# analog_v10.net
KiCad netlist of a schematic drawn in EAGLE
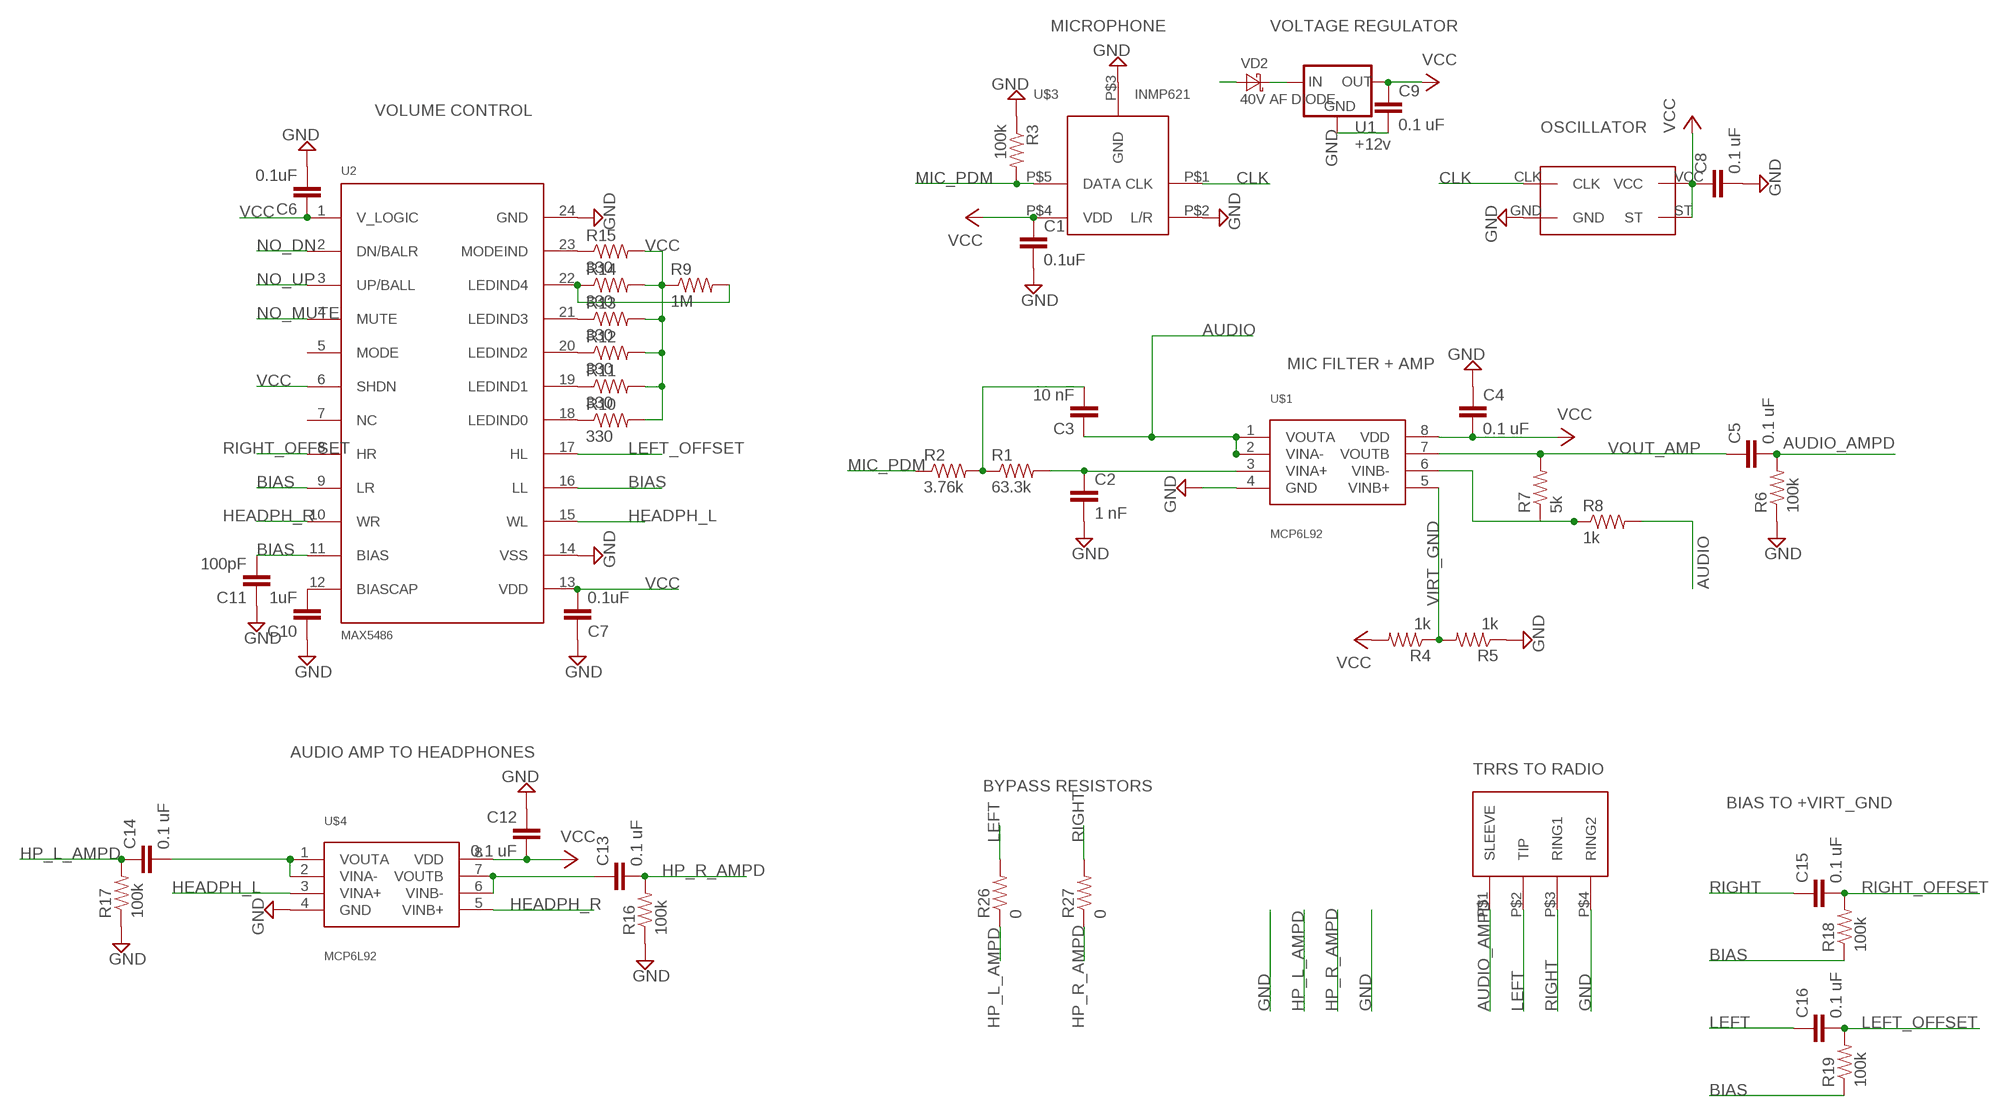
[diagram p0: schematic, sheet 1]

(export (version "E")
  (design (tool "Eeschema 10.0.6"))
  (components
    (comp (ref "C1")
      (value "0.1uF")
      (footprint "eagle-import:0805")
      (libsource (lib "eagle-import") (part "CAP0805"))
    )
    (comp (ref "C2")
      (value "1 nF")
      (footprint "eagle-import:0805")
      (libsource (lib "eagle-import") (part "CAP0805"))
    )
    (comp (ref "C3")
      (value "10 nF")
      (footprint "eagle-import:0805")
      (libsource (lib "eagle-import") (part "CAP0805"))
    )
    (comp (ref "C4")
      (value "0.1 uF")
      (footprint "eagle-import:0805")
      (libsource (lib "eagle-import") (part "CAP0805"))
    )
    (comp (ref "C5")
      (value "0.1 uF")
      (footprint "eagle-import:0805")
      (libsource (lib "eagle-import") (part "CAP0805"))
    )
    (comp (ref "C6")
      (value "0.1uF")
      (footprint "eagle-import:0805")
      (libsource (lib "eagle-import") (part "CAP0805"))
    )
    (comp (ref "C7")
      (value "0.1uF")
      (footprint "eagle-import:0805")
      (libsource (lib "eagle-import") (part "CAP0805"))
    )
    (comp (ref "C8")
      (value "0.1 uF")
      (footprint "eagle-import:0805")
      (libsource (lib "eagle-import") (part "CAP0805"))
    )
    (comp (ref "C9")
      (value "0.1 uF")
      (footprint "eagle-import:0805")
      (libsource (lib "eagle-import") (part "CAP0805"))
    )
    (comp (ref "C10")
      (value "1uF")
      (footprint "eagle-import:0805")
      (libsource (lib "eagle-import") (part "CAP0805"))
    )
    (comp (ref "C11")
      (value "100pF")
      (footprint "eagle-import:0805")
      (libsource (lib "eagle-import") (part "CAP0805"))
    )
    (comp (ref "C12")
      (value "0.1 uF")
      (footprint "eagle-import:0805")
      (libsource (lib "eagle-import") (part "CAP0805"))
    )
    (comp (ref "C13")
      (value "0.1 uF")
      (footprint "eagle-import:0805")
      (libsource (lib "eagle-import") (part "CAP0805"))
    )
    (comp (ref "C14")
      (value "0.1 uF")
      (footprint "eagle-import:0805")
      (libsource (lib "eagle-import") (part "CAP0805"))
    )
    (comp (ref "C15")
      (value "0.1 uF")
      (footprint "eagle-import:0805")
      (libsource (lib "eagle-import") (part "CAP0805"))
    )
    (comp (ref "C16")
      (value "0.1 uF")
      (footprint "eagle-import:0805")
      (libsource (lib "eagle-import") (part "CAP0805"))
    )
    (comp (ref "R1")
      (value "63.3k")
      (footprint "eagle-import:0805")
      (libsource (lib "eagle-import") (part "RESISTOR0805-RES"))
    )
    (comp (ref "R2")
      (value "3.76k")
      (footprint "eagle-import:0805")
      (libsource (lib "eagle-import") (part "RESISTOR0805-RES"))
    )
    (comp (ref "R3")
      (value "100k")
      (footprint "eagle-import:0805")
      (libsource (lib "eagle-import") (part "RESISTOR0805-RES"))
    )
    (comp (ref "R4")
      (value "1k")
      (footprint "eagle-import:0805")
      (libsource (lib "eagle-import") (part "RESISTOR0805-RES"))
    )
    (comp (ref "R5")
      (value "1k")
      (footprint "eagle-import:0805")
      (libsource (lib "eagle-import") (part "RESISTOR0805-RES"))
    )
    (comp (ref "R6")
      (value "100k")
      (footprint "eagle-import:0805")
      (libsource (lib "eagle-import") (part "SparkFun-Resistors_RESISTOR0805-RES"))
    )
    (comp (ref "R7")
      (value "5k")
      (footprint "eagle-import:0805")
      (libsource (lib "eagle-import") (part "SparkFun-Resistors_RESISTOR0805-RES"))
    )
    (comp (ref "R8")
      (value "1k")
      (footprint "eagle-import:0805")
      (libsource (lib "eagle-import") (part "SparkFun-Resistors_RESISTOR0805-RES"))
    )
    (comp (ref "R9")
      (value "1M")
      (footprint "eagle-import:0805")
      (libsource (lib "eagle-import") (part "RESISTOR0805-RES"))
    )
    (comp (ref "R10")
      (value "330")
      (footprint "eagle-import:0805")
      (libsource (lib "eagle-import") (part "RESISTOR0805-RES"))
    )
    (comp (ref "R11")
      (value "330")
      (footprint "eagle-import:0805")
      (libsource (lib "eagle-import") (part "RESISTOR0805-RES"))
    )
    (comp (ref "R12")
      (value "330")
      (footprint "eagle-import:0805")
      (libsource (lib "eagle-import") (part "RESISTOR0805-RES"))
    )
    (comp (ref "R13")
      (value "330")
      (footprint "eagle-import:0805")
      (libsource (lib "eagle-import") (part "RESISTOR0805-RES"))
    )
    (comp (ref "R14")
      (value "330")
      (footprint "eagle-import:0805")
      (libsource (lib "eagle-import") (part "RESISTOR0805-RES"))
    )
    (comp (ref "R15")
      (value "330")
      (footprint "eagle-import:0805")
      (libsource (lib "eagle-import") (part "RESISTOR0805-RES"))
    )
    (comp (ref "R16")
      (value "100k")
      (footprint "eagle-import:0805")
      (libsource (lib "eagle-import") (part "SparkFun-Resistors_RESISTOR0805-RES"))
    )
    (comp (ref "R17")
      (value "100k")
      (footprint "eagle-import:0805")
      (libsource (lib "eagle-import") (part "SparkFun-Resistors_RESISTOR0805-RES"))
    )
    (comp (ref "R18")
      (value "100k")
      (footprint "eagle-import:0805")
      (libsource (lib "eagle-import") (part "SparkFun-Resistors_RESISTOR0805-RES"))
    )
    (comp (ref "R19")
      (value "100k")
      (footprint "eagle-import:0805")
      (libsource (lib "eagle-import") (part "SparkFun-Resistors_RESISTOR0805-RES"))
    )
    (comp (ref "R26")
      (value "0")
      (footprint "eagle-import:0805")
      (libsource (lib "eagle-import") (part "RESISTOR0805-RES"))
    )
    (comp (ref "R27")
      (value "0")
      (footprint "eagle-import:0805")
      (libsource (lib "eagle-import") (part "RESISTOR0805-RES"))
    )
    (comp (ref "RADIO")
      (value "SJ-43514-SMT")
      (footprint "eagle-import:35MM_SMD_4WIRE")
      (libsource (lib "eagle-import") (part "SJ-43514-SMT"))
    )
    (comp (ref "U$1")
      (value "MCP6L92")
      (footprint "eagle-import:MSOP8")
      (libsource (lib "eagle-import") (part "MCP6L92"))
    )
    (comp (ref "U$2")
      (value "SG-210STF")
      (footprint "eagle-import:SG-210STF")
      (libsource (lib "eagle-import") (part "SG-210STF"))
    )
    (comp (ref "U$3")
      (value "INMP621")
      (footprint "eagle-import:CUSTOM_MIC")
      (libsource (lib "eagle-import") (part "INMP621"))
    )
    (comp (ref "U$4")
      (value "MCP6L92")
      (footprint "eagle-import:MSOP8")
      (libsource (lib "eagle-import") (part "MCP6L92"))
    )
    (comp (ref "U1")
      (value "+12v")
      (footprint "eagle-import:TO-252")
      (libsource (lib "eagle-import") (part "V_REG_78XX7812"))
    )
    (comp (ref "U2")
      (value "MAX5486")
      (footprint "eagle-import:TSSOP24")
      (libsource (lib "eagle-import") (part "MAX5486"))
    )
    (comp (ref "VD2")
      (value "40V AF DIODE")
      (footprint "eagle-import:SOD123")
      (libsource (lib "eagle-import") (part "DIODE-SCHOTTKY-SOD123"))
    )
  )
  (nets
    (net (code "1") (name "/AUDIO") (class "Default")
      (node (ref "C3") (pin "1") (pinfunction "1_1") (pintype "passive"))
      (node (ref "R8") (pin "2") (pinfunction "2_2") (pintype "passive"))
      (node (ref "U$1") (pin "1") (pinfunction "VOUTA_1") (pintype "bidirectional"))
      (node (ref "U$1") (pin "2") (pinfunction "VINA-_2") (pintype "bidirectional"))
    )
    (net (code "2") (name "/AUDIO_AMPD") (class "Default")
      (node (ref "C5") (pin "2") (pinfunction "2_2") (pintype "passive"))
      (node (ref "R6") (pin "2") (pinfunction "2_2") (pintype "passive"))
      (node (ref "RADIO") (pin "P$1") (pinfunction "SLEEVE_P$1") (pintype "bidirectional"))
    )
    (net (code "3") (name "/BIAS") (class "Default")
      (node (ref "C11") (pin "2") (pinfunction "2_2") (pintype "passive"))
      (node (ref "R18") (pin "1") (pinfunction "1_1") (pintype "passive"))
      (node (ref "R19") (pin "1") (pinfunction "1_1") (pintype "passive"))
      (node (ref "U2") (pin "11") (pinfunction "BIAS_11") (pintype "bidirectional"))
      (node (ref "U2") (pin "16") (pinfunction "LL_16") (pintype "input"))
      (node (ref "U2") (pin "9") (pinfunction "LR_9") (pintype "output"))
    )
    (net (code "4") (name "/CLK") (class "Default")
      (node (ref "U$2") (pin "CLK") (pinfunction "CLK_CLK") (pintype "bidirectional"))
      (node (ref "U$3") (pin "P$1") (pinfunction "CLK_P$1") (pintype "bidirectional"))
    )
    (net (code "5") (name "/HEADPH_L") (class "Default")
      (node (ref "U$4") (pin "3") (pinfunction "VINA+_3") (pintype "bidirectional"))
      (node (ref "U2") (pin "15") (pinfunction "WL_15") (pintype "power_in"))
    )
    (net (code "6") (name "/HEADPH_R") (class "Default")
      (node (ref "U$4") (pin "5") (pinfunction "VINB+_5") (pintype "bidirectional"))
      (node (ref "U2") (pin "10") (pinfunction "WR_10") (pintype "output"))
    )
    (net (code "7") (name "/HP_L_AMPD") (class "Default")
      (node (ref "C14") (pin "1") (pinfunction "1_1") (pintype "passive"))
      (node (ref "R17") (pin "2") (pinfunction "2_2") (pintype "passive"))
      (node (ref "R26") (pin "1") (pinfunction "1_1") (pintype "passive"))
    )
    (net (code "8") (name "/HP_R_AMPD") (class "Default")
      (node (ref "C13") (pin "2") (pinfunction "2_2") (pintype "passive"))
      (node (ref "R16") (pin "2") (pinfunction "2_2") (pintype "passive"))
      (node (ref "R27") (pin "1") (pinfunction "1_1") (pintype "passive"))
    )
    (net (code "9") (name "/LEFT") (class "Default")
      (node (ref "C16") (pin "1") (pinfunction "1_1") (pintype "passive"))
      (node (ref "R26") (pin "2") (pinfunction "2_2") (pintype "passive"))
      (node (ref "RADIO") (pin "P$2") (pinfunction "TIP_P$2") (pintype "bidirectional"))
    )
    (net (code "10") (name "/LEFT_OFFSET") (class "Default")
      (node (ref "C16") (pin "2") (pinfunction "2_2") (pintype "passive"))
      (node (ref "R19") (pin "2") (pinfunction "2_2") (pintype "passive"))
      (node (ref "U2") (pin "17") (pinfunction "HL_17") (pintype "input"))
    )
    (net (code "11") (name "/MIC_PDM") (class "Default")
      (node (ref "R2") (pin "1") (pinfunction "1_1") (pintype "passive"))
      (node (ref "R3") (pin "2") (pinfunction "2_2") (pintype "passive"))
      (node (ref "U$3") (pin "P$5") (pinfunction "DATA_P$5") (pintype "bidirectional"))
    )
    (net (code "12") (name "/NO_DN") (class "Default")
      (node (ref "U2") (pin "2") (pinfunction "DN/BALR_2") (pintype "input"))
    )
    (net (code "13") (name "/NO_MUTE") (class "Default")
      (node (ref "U2") (pin "4") (pinfunction "MUTE_4") (pintype "input"))
    )
    (net (code "14") (name "/NO_UP") (class "Default")
      (node (ref "U2") (pin "3") (pinfunction "UP/BALL_3") (pintype "input"))
    )
    (net (code "15") (name "/RIGHT") (class "Default")
      (node (ref "C15") (pin "1") (pinfunction "1_1") (pintype "passive"))
      (node (ref "R27") (pin "2") (pinfunction "2_2") (pintype "passive"))
      (node (ref "RADIO") (pin "P$3") (pinfunction "RING1_P$3") (pintype "bidirectional"))
    )
    (net (code "16") (name "/RIGHT_OFFSET") (class "Default")
      (node (ref "C15") (pin "2") (pinfunction "2_2") (pintype "passive"))
      (node (ref "R18") (pin "2") (pinfunction "2_2") (pintype "passive"))
      (node (ref "U2") (pin "8") (pinfunction "HR_8") (pintype "output"))
    )
    (net (code "17") (name "/VIRT_GND") (class "Default")
      (node (ref "R4") (pin "1") (pinfunction "1_1") (pintype "passive"))
      (node (ref "R5") (pin "2") (pinfunction "2_2") (pintype "passive"))
      (node (ref "U$1") (pin "5") (pinfunction "VINB+_5") (pintype "bidirectional"))
    )
    (net (code "18") (name "/VOUT_AMP") (class "Default")
      (node (ref "C5") (pin "1") (pinfunction "1_1") (pintype "passive"))
      (node (ref "R7") (pin "2") (pinfunction "2_2") (pintype "passive"))
      (node (ref "U$1") (pin "7") (pinfunction "VOUTB_7") (pintype "bidirectional"))
    )
    (net (code "19") (name "GND") (class "Default")
      (node (ref "C1") (pin "2") (pinfunction "2_2") (pintype "passive"))
      (node (ref "C10") (pin "1") (pinfunction "1_1") (pintype "passive"))
      (node (ref "C11") (pin "1") (pinfunction "1_1") (pintype "passive"))
      (node (ref "C12") (pin "1") (pinfunction "1_1") (pintype "passive"))
      (node (ref "C2") (pin "2") (pinfunction "2_2") (pintype "passive"))
      (node (ref "C4") (pin "1") (pinfunction "1_1") (pintype "passive"))
      (node (ref "C6") (pin "2") (pinfunction "2_2") (pintype "passive"))
      (node (ref "C7") (pin "1") (pinfunction "1_1") (pintype "passive"))
      (node (ref "C8") (pin "2") (pinfunction "2_2") (pintype "passive"))
      (node (ref "C9") (pin "2") (pinfunction "2_2") (pintype "passive"))
      (node (ref "R16") (pin "1") (pinfunction "1_1") (pintype "passive"))
      (node (ref "R17") (pin "1") (pinfunction "1_1") (pintype "passive"))
      (node (ref "R3") (pin "1") (pinfunction "1_1") (pintype "passive"))
      (node (ref "R5") (pin "1") (pinfunction "1_1") (pintype "passive"))
      (node (ref "R6") (pin "1") (pinfunction "1_1") (pintype "passive"))
      (node (ref "RADIO") (pin "P$4") (pinfunction "RING2_P$4") (pintype "bidirectional"))
      (node (ref "U$1") (pin "4") (pinfunction "GND_4") (pintype "bidirectional"))
      (node (ref "U$2") (pin "GND") (pinfunction "GND_GND") (pintype "bidirectional"))
      (node (ref "U$3") (pin "P$2") (pinfunction "L/R_P$2") (pintype "bidirectional"))
      (node (ref "U$3") (pin "P$3") (pinfunction "GND_P$3") (pintype "bidirectional"))
      (node (ref "U$4") (pin "4") (pinfunction "GND_4") (pintype "bidirectional"))
      (node (ref "U1") (pin "3") (pinfunction "GND_3") (pintype "input"))
      (node (ref "U2") (pin "14") (pinfunction "VSS_14") (pintype "power_in"))
      (node (ref "U2") (pin "24") (pinfunction "GND_24") (pintype "bidirectional"))
    )
    (net (code "20") (name "Net-(C3-Pad2)") (class "Default")
      (node (ref "C3") (pin "2") (pinfunction "2_2") (pintype "passive"))
      (node (ref "R1") (pin "1") (pinfunction "1_1") (pintype "passive"))
      (node (ref "R2") (pin "2") (pinfunction "2_2") (pintype "passive"))
    )
    (net (code "21") (name "Net-(U$1-VINA+)") (class "Default")
      (node (ref "C2") (pin "1") (pinfunction "1_1") (pintype "passive"))
      (node (ref "R1") (pin "2") (pinfunction "2_2") (pintype "passive"))
      (node (ref "U$1") (pin "3") (pinfunction "VINA+_3") (pintype "bidirectional"))
    )
    (net (code "22") (name "Net-(U$1-VINB-)") (class "Default")
      (node (ref "R7") (pin "1") (pinfunction "1_1") (pintype "passive"))
      (node (ref "R8") (pin "1") (pinfunction "1_1") (pintype "passive"))
      (node (ref "U$1") (pin "6") (pinfunction "VINB-_6") (pintype "bidirectional"))
    )
    (net (code "23") (name "Net-(U$4-VINA-)") (class "Default")
      (node (ref "C14") (pin "2") (pinfunction "2_2") (pintype "passive"))
      (node (ref "U$4") (pin "1") (pinfunction "VOUTA_1") (pintype "bidirectional"))
      (node (ref "U$4") (pin "2") (pinfunction "VINA-_2") (pintype "bidirectional"))
    )
    (net (code "24") (name "Net-(U$4-VINB-)") (class "Default")
      (node (ref "C13") (pin "1") (pinfunction "1_1") (pintype "passive"))
      (node (ref "U$4") (pin "6") (pinfunction "VINB-_6") (pintype "bidirectional"))
      (node (ref "U$4") (pin "7") (pinfunction "VOUTB_7") (pintype "bidirectional"))
    )
    (net (code "25") (name "Net-(U1-IN)") (class "Default")
      (node (ref "U1") (pin "2") (pinfunction "IN_2") (pintype "input"))
      (node (ref "VD2") (pin "C") (pinfunction "C_C") (pintype "passive"))
    )
    (net (code "26") (name "Net-(U2-BIASCAP)") (class "Default")
      (node (ref "C10") (pin "2") (pinfunction "2_2") (pintype "passive"))
      (node (ref "U2") (pin "12") (pinfunction "BIASCAP_12") (pintype "input"))
    )
    (net (code "27") (name "Net-(U2-LEDIND0)") (class "Default")
      (node (ref "R10") (pin "1") (pinfunction "1_1") (pintype "passive"))
      (node (ref "U2") (pin "18") (pinfunction "LEDIND0_18") (pintype "input"))
    )
    (net (code "28") (name "Net-(U2-LEDIND1)") (class "Default")
      (node (ref "R11") (pin "1") (pinfunction "1_1") (pintype "passive"))
      (node (ref "U2") (pin "19") (pinfunction "LEDIND1_19") (pintype "bidirectional"))
    )
    (net (code "29") (name "Net-(U2-LEDIND2)") (class "Default")
      (node (ref "R12") (pin "1") (pinfunction "1_1") (pintype "passive"))
      (node (ref "U2") (pin "20") (pinfunction "LEDIND2_20") (pintype "bidirectional"))
    )
    (net (code "30") (name "Net-(U2-LEDIND3)") (class "Default")
      (node (ref "R13") (pin "1") (pinfunction "1_1") (pintype "passive"))
      (node (ref "U2") (pin "21") (pinfunction "LEDIND3_21") (pintype "bidirectional"))
    )
    (net (code "31") (name "Net-(U2-LEDIND4)") (class "Default")
      (node (ref "R14") (pin "1") (pinfunction "1_1") (pintype "passive"))
      (node (ref "R9") (pin "2") (pinfunction "2_2") (pintype "passive"))
      (node (ref "U2") (pin "22") (pinfunction "LEDIND4_22") (pintype "input"))
    )
    (net (code "32") (name "Net-(U2-MODEIND)") (class "Default")
      (node (ref "R15") (pin "1") (pinfunction "1_1") (pintype "passive"))
      (node (ref "U2") (pin "23") (pinfunction "MODEIND_23") (pintype "input"))
    )
    (net (code "33") (name "VCC") (class "Default")
      (node (ref "C1") (pin "1") (pinfunction "1_1") (pintype "passive"))
      (node (ref "C12") (pin "2") (pinfunction "2_2") (pintype "passive"))
      (node (ref "C4") (pin "2") (pinfunction "2_2") (pintype "passive"))
      (node (ref "C6") (pin "1") (pinfunction "1_1") (pintype "passive"))
      (node (ref "C7") (pin "2") (pinfunction "2_2") (pintype "passive"))
      (node (ref "C8") (pin "1") (pinfunction "1_1") (pintype "passive"))
      (node (ref "C9") (pin "1") (pinfunction "1_1") (pintype "passive"))
      (node (ref "R10") (pin "2") (pinfunction "2_2") (pintype "passive"))
      (node (ref "R11") (pin "2") (pinfunction "2_2") (pintype "passive"))
      (node (ref "R12") (pin "2") (pinfunction "2_2") (pintype "passive"))
      (node (ref "R13") (pin "2") (pinfunction "2_2") (pintype "passive"))
      (node (ref "R14") (pin "2") (pinfunction "2_2") (pintype "passive"))
      (node (ref "R15") (pin "2") (pinfunction "2_2") (pintype "passive"))
      (node (ref "R4") (pin "2") (pinfunction "2_2") (pintype "passive"))
      (node (ref "R9") (pin "1") (pinfunction "1_1") (pintype "passive"))
      (node (ref "U$1") (pin "8") (pinfunction "VDD_8") (pintype "bidirectional"))
      (node (ref "U$2") (pin "ST") (pinfunction "ST_ST") (pintype "bidirectional"))
      (node (ref "U$2") (pin "VCC") (pinfunction "VCC_VCC") (pintype "bidirectional"))
      (node (ref "U$3") (pin "P$4") (pinfunction "VDD_P$4") (pintype "bidirectional"))
      (node (ref "U$4") (pin "8") (pinfunction "VDD_8") (pintype "bidirectional"))
      (node (ref "U1") (pin "1") (pinfunction "OUT_1") (pintype "passive"))
      (node (ref "U2") (pin "1") (pinfunction "V_LOGIC_1") (pintype "input"))
      (node (ref "U2") (pin "13") (pinfunction "VDD_13") (pintype "power_in"))
      (node (ref "U2") (pin "6") (pinfunction "SHDN_6") (pintype "input"))
    )
    (net (code "34") (name "unconnected-(U2-MODE-Pad5)") (class "Default")
      (node (ref "U2") (pin "5") (pinfunction "MODE_5") (pintype "input"))
    )
    (net (code "35") (name "unconnected-(U2-NC-Pad7)") (class "Default")
      (node (ref "U2") (pin "7") (pinfunction "NC_7") (pintype "input"))
    )
    (net (code "36") (name "unconnected-(VD2-PadA)") (class "Default")
      (node (ref "VD2") (pin "A") (pinfunction "A_A") (pintype "passive"))
    )
  )
)
